# ControlHVAC.net
KiCad netlist of a schematic drawn in EAGLE
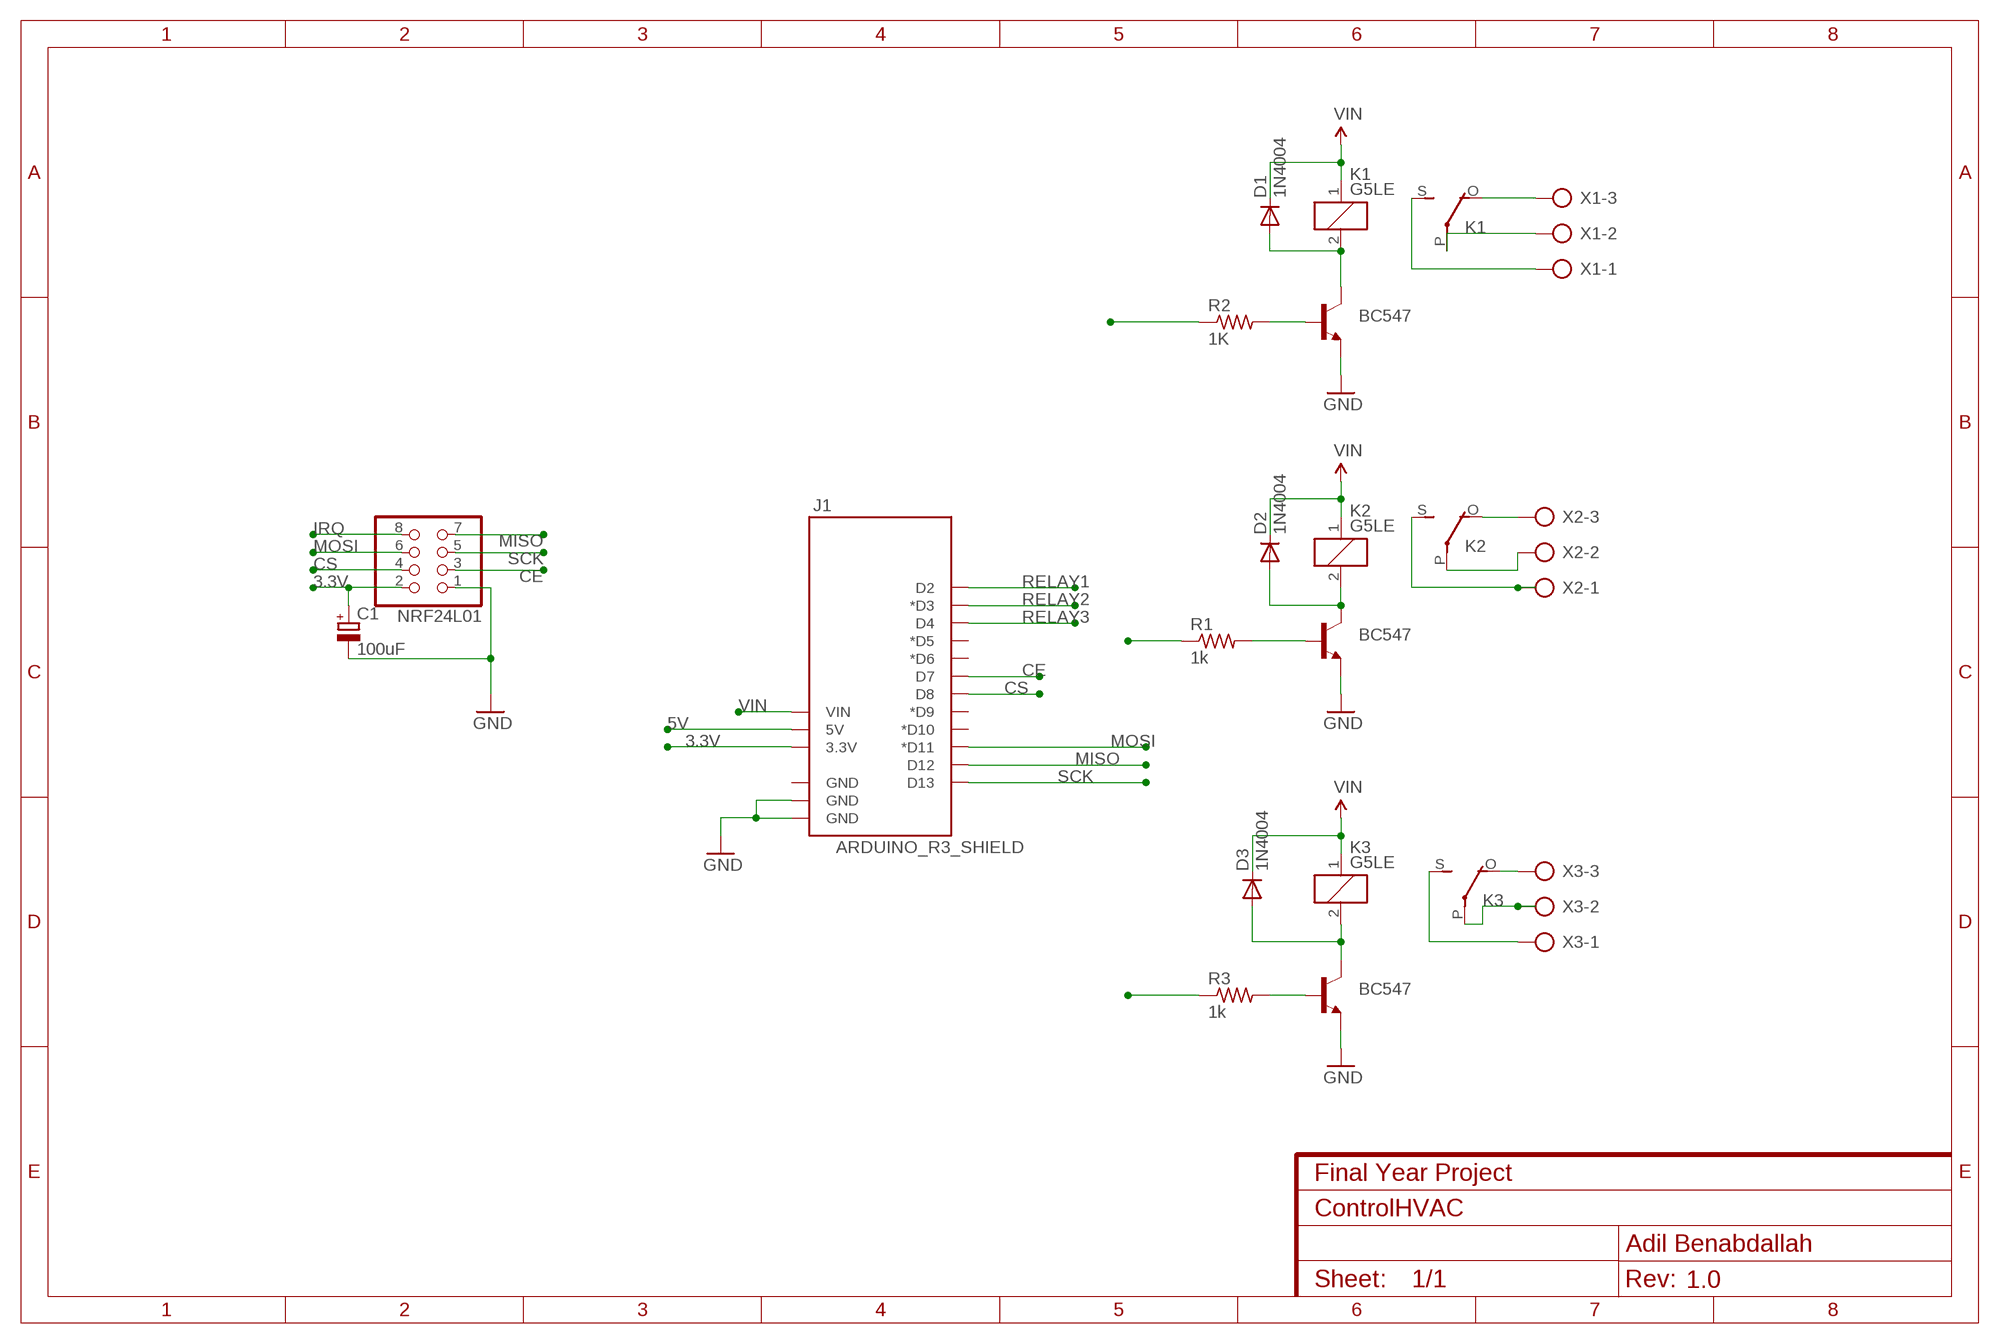
[diagram p0: schematic, sheet 1]

(export (version "E")
  (design (tool "Eeschema 10.0.6"))
  (components
    (comp (ref "C1")
      (value "100uF")
      (footprint "eagle-import:E5-6")
      (libsource (lib "eagle-import") (part "CPOL-EUE5-6"))
    )
    (comp (ref "D1")
      (value "1N4004")
      (footprint "eagle-import:DO41-10")
      (libsource (lib "eagle-import") (part "1N4004"))
    )
    (comp (ref "D2")
      (value "1N4004")
      (footprint "eagle-import:DO41-10")
      (libsource (lib "eagle-import") (part "1N4004"))
    )
    (comp (ref "D3")
      (value "1N4004")
      (footprint "eagle-import:DO41-10")
      (libsource (lib "eagle-import") (part "1N4004"))
    )
    (comp (ref "J1")
      (value "ARDUINO_R3_SHIELD")
      (footprint "eagle-import:UNO_R3_SHIELD")
      (libsource (lib "eagle-import") (part "SINOVA_SHIELD"))
    )
    (comp (ref "K1")
      (value "G5LE")
      (footprint "eagle-import:G5LE")
      (libsource (lib "eagle-import") (part "G5LE"))
    )
    (comp (ref "K2")
      (value "G5LE")
      (footprint "eagle-import:G5LE")
      (libsource (lib "eagle-import") (part "G5LE"))
    )
    (comp (ref "K3")
      (value "G5LE")
      (footprint "eagle-import:G5LE")
      (libsource (lib "eagle-import") (part "G5LE"))
    )
    (comp (ref "NRF24L01")
      (value "PINHD-2X4")
      (footprint "eagle-import:2X04")
      (libsource (lib "eagle-import") (part "PINHD-2X4"))
    )
    (comp (ref "R1")
      (value "1k")
      (footprint "eagle-import:0204_7")
      (libsource (lib "eagle-import") (part "R-US_0204/7"))
    )
    (comp (ref "R2")
      (value "1K")
      (footprint "eagle-import:0204_7")
      (libsource (lib "eagle-import") (part "R-US_0204/7"))
    )
    (comp (ref "R3")
      (value "1k")
      (footprint "eagle-import:0204_7")
      (libsource (lib "eagle-import") (part "R-US_0204/7"))
    )
    (comp (ref "T1")
      (value "BC547")
      (footprint "eagle-import:TO92")
      (libsource (lib "eagle-import") (part "BC547"))
    )
    (comp (ref "T2")
      (value "BC547")
      (footprint "eagle-import:TO92")
      (libsource (lib "eagle-import") (part "BC547"))
    )
    (comp (ref "T3")
      (value "BC547")
      (footprint "eagle-import:TO92")
      (libsource (lib "eagle-import") (part "BC547"))
    )
    (comp (ref "X1")
      (value "AK500/3-H")
      (footprint "eagle-import:AK500_3-H")
      (libsource (lib "eagle-import") (part "AK500/3-H"))
    )
    (comp (ref "X2")
      (value "AK500/3-H")
      (footprint "eagle-import:AK500_3-H")
      (libsource (lib "eagle-import") (part "AK500/3-H"))
    )
    (comp (ref "X3")
      (value "AK500/3-H")
      (footprint "eagle-import:AK500_3-H")
      (libsource (lib "eagle-import") (part "AK500/3-H"))
    )
  )
  (nets
    (net (code "1") (name "/3.3V") (class "Default")
      (node (ref "C1") (pin "+") (pinfunction "+_+") (pintype "passive"))
      (node (ref "J1") (pin "3.3V") (pinfunction "3.3V_3.3V") (pintype "bidirectional"))
      (node (ref "NRF24L01") (pin "2") (pinfunction "2_2") (pintype "passive"))
    )
    (net (code "2") (name "/5V") (class "Default")
      (node (ref "J1") (pin "5V") (pinfunction "5V_5V") (pintype "bidirectional"))
    )
    (net (code "3") (name "/CE") (class "Default")
      (node (ref "J1") (pin "D7") (pinfunction "D7_D7") (pintype "bidirectional"))
      (node (ref "NRF24L01") (pin "3") (pinfunction "3_3") (pintype "passive"))
    )
    (net (code "4") (name "/CS") (class "Default")
      (node (ref "J1") (pin "D8") (pinfunction "D8_D8") (pintype "bidirectional"))
      (node (ref "NRF24L01") (pin "4") (pinfunction "4_4") (pintype "passive"))
    )
    (net (code "5") (name "/IRQ") (class "Default")
      (node (ref "NRF24L01") (pin "8") (pinfunction "8_8") (pintype "passive"))
    )
    (net (code "6") (name "/MISO") (class "Default")
      (node (ref "J1") (pin "D12") (pinfunction "D12_D12") (pintype "bidirectional"))
      (node (ref "NRF24L01") (pin "7") (pinfunction "7_7") (pintype "passive"))
    )
    (net (code "7") (name "/MOSI") (class "Default")
      (node (ref "J1") (pin "D11") (pinfunction "*D11_D11") (pintype "bidirectional"))
      (node (ref "NRF24L01") (pin "6") (pinfunction "6_6") (pintype "passive"))
    )
    (net (code "8") (name "/RELAY1") (class "Default")
      (node (ref "J1") (pin "D2") (pinfunction "D2_D2") (pintype "bidirectional"))
      (node (ref "R2") (pin "1") (pinfunction "1_1") (pintype "passive"))
    )
    (net (code "9") (name "/RELAY2") (class "Default")
      (node (ref "J1") (pin "D3") (pinfunction "*D3_D3") (pintype "bidirectional"))
      (node (ref "R1") (pin "1") (pinfunction "1_1") (pintype "passive"))
    )
    (net (code "10") (name "/RELAY3") (class "Default")
      (node (ref "J1") (pin "D4") (pinfunction "D4_D4") (pintype "bidirectional"))
      (node (ref "R3") (pin "1") (pinfunction "1_1") (pintype "passive"))
    )
    (net (code "11") (name "/SCK") (class "Default")
      (node (ref "J1") (pin "D13") (pinfunction "D13_D13") (pintype "bidirectional"))
      (node (ref "NRF24L01") (pin "5") (pinfunction "5_5") (pintype "passive"))
    )
    (net (code "12") (name "GND") (class "Default")
      (node (ref "C1") (pin "-") (pinfunction "-_-") (pintype "passive"))
      (node (ref "J1") (pin "GND@0") (pinfunction "GND_GND@0") (pintype "bidirectional"))
      (node (ref "J1") (pin "GND@1") (pinfunction "GND_GND@1") (pintype "bidirectional"))
      (node (ref "NRF24L01") (pin "1") (pinfunction "1_1") (pintype "passive"))
      (node (ref "T1") (pin "1") (pinfunction "E_1") (pintype "passive"))
      (node (ref "T2") (pin "1") (pinfunction "E_1") (pintype "passive"))
      (node (ref "T3") (pin "1") (pinfunction "E_1") (pintype "passive"))
    )
    (net (code "13") (name "Net-(T1-B)") (class "Default")
      (node (ref "R2") (pin "2") (pinfunction "2_2") (pintype "passive"))
      (node (ref "T1") (pin "2") (pinfunction "B_2") (pintype "passive"))
    )
    (net (code "14") (name "Net-(T1-C)") (class "Default")
      (node (ref "D1") (pin "A") (pinfunction "A_A") (pintype "passive"))
      (node (ref "K1") (pin "2") (pinfunction "2_2") (pintype "passive"))
      (node (ref "T1") (pin "3") (pinfunction "C_3") (pintype "passive"))
    )
    (net (code "15") (name "Net-(T2-B)") (class "Default")
      (node (ref "R1") (pin "2") (pinfunction "2_2") (pintype "passive"))
      (node (ref "T2") (pin "2") (pinfunction "B_2") (pintype "passive"))
    )
    (net (code "16") (name "Net-(T2-C)") (class "Default")
      (node (ref "D2") (pin "A") (pinfunction "A_A") (pintype "passive"))
      (node (ref "K2") (pin "2") (pinfunction "2_2") (pintype "passive"))
      (node (ref "T2") (pin "3") (pinfunction "C_3") (pintype "passive"))
    )
    (net (code "17") (name "Net-(T3-B)") (class "Default")
      (node (ref "R3") (pin "2") (pinfunction "2_2") (pintype "passive"))
      (node (ref "T3") (pin "2") (pinfunction "B_2") (pintype "passive"))
    )
    (net (code "18") (name "Net-(T3-C)") (class "Default")
      (node (ref "D3") (pin "A") (pinfunction "A_A") (pintype "passive"))
      (node (ref "K3") (pin "2") (pinfunction "2_2") (pintype "passive"))
      (node (ref "T3") (pin "3") (pinfunction "C_3") (pintype "passive"))
    )
    (net (code "19") (name "Net-(X1A-KL)") (class "Default")
      (node (ref "K1") (pin "S") (pinfunction "S_S") (pintype "passive"))
      (node (ref "X1") (pin "1") (pinfunction "KL_1") (pintype "passive"))
    )
    (net (code "20") (name "Net-(X1B-KL)") (class "Default")
      (node (ref "K1") (pin "P") (pinfunction "P_P") (pintype "passive"))
      (node (ref "X1") (pin "2") (pinfunction "KL_2") (pintype "passive"))
    )
    (net (code "21") (name "Net-(X1C-KL)") (class "Default")
      (node (ref "K1") (pin "O") (pinfunction "O_O") (pintype "passive"))
      (node (ref "X1") (pin "3") (pinfunction "KL_3") (pintype "passive"))
    )
    (net (code "22") (name "Net-(X2A-KL)") (class "Default")
      (node (ref "K2") (pin "S") (pinfunction "S_S") (pintype "passive"))
      (node (ref "X2") (pin "1") (pinfunction "KL_1") (pintype "passive"))
    )
    (net (code "23") (name "Net-(X2B-KL)") (class "Default")
      (node (ref "K2") (pin "P") (pinfunction "P_P") (pintype "passive"))
      (node (ref "X2") (pin "2") (pinfunction "KL_2") (pintype "passive"))
    )
    (net (code "24") (name "Net-(X2C-KL)") (class "Default")
      (node (ref "K2") (pin "O") (pinfunction "O_O") (pintype "passive"))
      (node (ref "X2") (pin "3") (pinfunction "KL_3") (pintype "passive"))
    )
    (net (code "25") (name "Net-(X3A-KL)") (class "Default")
      (node (ref "K3") (pin "S") (pinfunction "S_S") (pintype "passive"))
      (node (ref "X3") (pin "1") (pinfunction "KL_1") (pintype "passive"))
    )
    (net (code "26") (name "Net-(X3B-KL)") (class "Default")
      (node (ref "K3") (pin "P") (pinfunction "P_P") (pintype "passive"))
      (node (ref "X3") (pin "2") (pinfunction "KL_2") (pintype "passive"))
    )
    (net (code "27") (name "Net-(X3C-KL)") (class "Default")
      (node (ref "K3") (pin "O") (pinfunction "O_O") (pintype "passive"))
      (node (ref "X3") (pin "3") (pinfunction "KL_3") (pintype "passive"))
    )
    (net (code "28") (name "VIN") (class "Default")
      (node (ref "D1") (pin "C") (pinfunction "C_C") (pintype "passive"))
      (node (ref "D2") (pin "C") (pinfunction "C_C") (pintype "passive"))
      (node (ref "D3") (pin "C") (pinfunction "C_C") (pintype "passive"))
      (node (ref "J1") (pin "VIN") (pinfunction "VIN_VIN") (pintype "bidirectional"))
      (node (ref "K1") (pin "1") (pinfunction "1_1") (pintype "passive"))
      (node (ref "K2") (pin "1") (pinfunction "1_1") (pintype "passive"))
      (node (ref "K3") (pin "1") (pinfunction "1_1") (pintype "passive"))
    )
    (net (code "29") (name "unconnected-(J1-*D5-PadD5)") (class "Default")
      (node (ref "J1") (pin "D5") (pinfunction "*D5_D5") (pintype "bidirectional"))
    )
    (net (code "30") (name "unconnected-(J1-*D6-PadD6)") (class "Default")
      (node (ref "J1") (pin "D6") (pinfunction "*D6_D6") (pintype "bidirectional"))
    )
    (net (code "31") (name "unconnected-(J1-*D9-PadD9)") (class "Default")
      (node (ref "J1") (pin "D9") (pinfunction "*D9_D9") (pintype "bidirectional"))
    )
    (net (code "32") (name "unconnected-(J1-*D10-PadD10)") (class "Default")
      (node (ref "J1") (pin "D10") (pinfunction "*D10_D10") (pintype "bidirectional"))
    )
    (net (code "33") (name "unconnected-(J1-GND-PadGND@2)") (class "Default")
      (node (ref "J1") (pin "GND@2") (pinfunction "GND_GND@2") (pintype "bidirectional"))
    )
  )
)
